# FLS_ADC_A_POWER_SUPPLY.net
KiCad netlist of a schematic drawn in Altium Designer
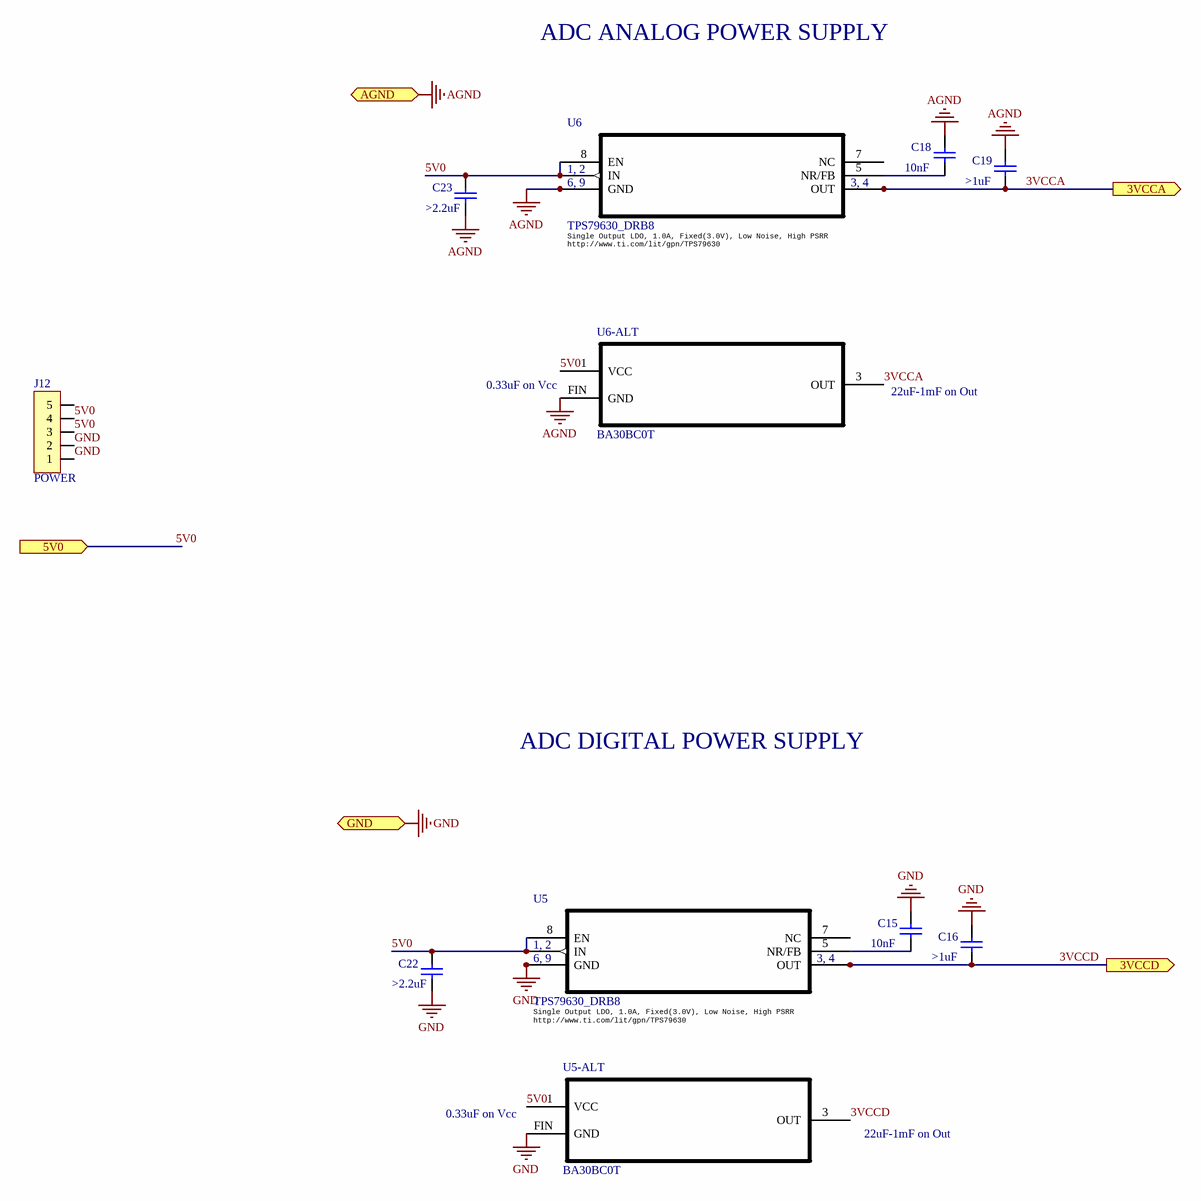
[diagram p0: FLS ADC_A POWER SUPPLY.SchDoc]

(export (version "E")
  (design (tool "Eeschema 10.0.6"))
  (components
    (comp (ref "C15")
      (value "10nF")
      (footprint "1608[0603]")
      (description "CAP CER 0.22UF 50V 10% X7R 0805")
      (fields
        (field (name "DIGI-KEY PART NUMBER") "587-1287-6-ND")
        (field (name "PUBLISHER") "Altium Limited")
      )
      (libsource (lib "Miscellaneous Devices") (part "Cap"))
    )
    (comp (ref "C16")
      (value ">1uF")
      (footprint "0805 slim outer")
      (description "CAP CER 0.22UF 50V 10% X7R 0805")
      (fields
        (field (name "DIGI-KEY PART NUMBER") "587-1287-6-ND")
        (field (name "PUBLISHER") "Altium Limited")
      )
      (libsource (lib "Miscellaneous Devices") (part "Cap"))
    )
    (comp (ref "C18")
      (value "10nF")
      (footprint "1608[0603]")
      (description "CAP CER 0.22UF 50V 10% X7R 0805")
      (fields
        (field (name "DIGI-KEY PART NUMBER") "587-1287-6-ND")
        (field (name "PUBLISHER") "Altium Limited")
      )
      (libsource (lib "Miscellaneous Devices") (part "Cap"))
    )
    (comp (ref "C19")
      (value ">1uF")
      (footprint "0805 slim outer")
      (description "CAP CER 0.22UF 50V 10% X7R 0805")
      (fields
        (field (name "DIGI-KEY PART NUMBER") "587-1287-6-ND")
        (field (name "PUBLISHER") "Altium Limited")
      )
      (libsource (lib "Miscellaneous Devices") (part "Cap"))
    )
    (comp (ref "C22")
      (value ">2.2uF")
      (footprint "1608[0603]")
      (description "CAP CER 0.22UF 50V 10% X7R 0805")
      (fields
        (field (name "DIGI-KEY PART NUMBER") "587-1287-6-ND")
        (field (name "PUBLISHER") "Altium Limited")
      )
      (libsource (lib "Miscellaneous Devices") (part "Cap"))
    )
    (comp (ref "C23")
      (value ">2.2uF")
      (footprint "1608[0603]")
      (description "CAP CER 0.22UF 50V 10% X7R 0805")
      (fields
        (field (name "DIGI-KEY PART NUMBER") "587-1287-6-ND")
        (field (name "PUBLISHER") "Altium Limited")
      )
      (libsource (lib "Miscellaneous Devices") (part "Cap"))
    )
    (comp (ref "J12") (value "POWER") (footprint "SIP5") (libsource (lib "FLS ADC_A") (part "CON5")))
    (comp (ref "U5")
      (value "TPS79630_DRB8")
      (footprint "DRB8_2P4X1P65")
      (description "Single Output LDO, 1.0A, Fixed(3.0V), Low Noise, High PSRR")
      (fields (field (name "DATASHEET URL") "http://www.ti.com/lit/gpn/TPS79630"))
      (libsource (lib "FLS ADC_A") (part "TPS79630_DRB8"))
    )
    (comp (ref "U5-ALT")
      (value "BA30BC0T")
      (footprint "TO252-3")
      (libsource (lib "FLS ADC_A") (part "BA30BC0T"))
    )
    (comp (ref "U6")
      (value "TPS79630_DRB8")
      (footprint "DRB8_2P4X1P65")
      (description "Single Output LDO, 1.0A, Fixed(3.0V), Low Noise, High PSRR")
      (fields (field (name "DATASHEET URL") "http://www.ti.com/lit/gpn/TPS79630"))
      (libsource (lib "FLS ADC_A") (part "TPS79630_DRB8"))
    )
    (comp (ref "U6-ALT")
      (value "BA30BC0T")
      (footprint "TO252-3")
      (libsource (lib "FLS ADC_A") (part "BA30BC0T"))
    )
  )
  (nets
    (net (code "1") (name "/3VCCA") (class "Default")
      (node (ref "C19") (pin "1") (pinfunction "1_1") (pintype "passive"))
      (node (ref "U6") (pin "3") (pinfunction "OUT_3") (pintype "passive"))
      (node (ref "U6") (pin "4") (pinfunction "OUT_4") (pintype "passive"))
      (node (ref "U6-ALT") (pin "3") (pinfunction "OUT_3") (pintype "passive"))
    )
    (net (code "2") (name "/3VCCD") (class "Default")
      (node (ref "C16") (pin "1") (pinfunction "1_1") (pintype "passive"))
      (node (ref "U5") (pin "3") (pinfunction "OUT_3") (pintype "passive"))
      (node (ref "U5") (pin "4") (pinfunction "OUT_4") (pintype "passive"))
      (node (ref "U5-ALT") (pin "3") (pinfunction "OUT_3") (pintype "passive"))
    )
    (net (code "3") (name "/5V0") (class "Default")
      (node (ref "C22") (pin "2") (pinfunction "2_2") (pintype "passive"))
      (node (ref "C23") (pin "2") (pinfunction "2_2") (pintype "passive"))
      (node (ref "J12") (pin "3") (pinfunction "3_3") (pintype "passive"))
      (node (ref "J12") (pin "4") (pinfunction "4_4") (pintype "passive"))
      (node (ref "U5") (pin "1") (pinfunction "IN_1") (pintype "output"))
      (node (ref "U5") (pin "2") (pinfunction "IN_2") (pintype "output"))
      (node (ref "U5") (pin "8") (pinfunction "EN_8") (pintype "passive"))
      (node (ref "U5-ALT") (pin "1") (pinfunction "VCC_1") (pintype "passive"))
      (node (ref "U6") (pin "1") (pinfunction "IN_1") (pintype "output"))
      (node (ref "U6") (pin "2") (pinfunction "IN_2") (pintype "output"))
      (node (ref "U6") (pin "8") (pinfunction "EN_8") (pintype "passive"))
      (node (ref "U6-ALT") (pin "1") (pinfunction "VCC_1") (pintype "passive"))
    )
    (net (code "4") (name "AGND") (class "Default")
      (node (ref "C18") (pin "2") (pinfunction "2_2") (pintype "passive"))
      (node (ref "C19") (pin "2") (pinfunction "2_2") (pintype "passive"))
      (node (ref "C23") (pin "1") (pinfunction "1_1") (pintype "passive"))
      (node (ref "U6") (pin "6") (pinfunction "GND_6") (pintype "power_in"))
      (node (ref "U6") (pin "9") (pinfunction "9_9") (pintype "power_in"))
      (node (ref "U6") (pin "V_1") (pinfunction "V_1_V_1") (pintype "power_in"))
      (node (ref "U6") (pin "V_2") (pinfunction "V_2_V_2") (pintype "power_in"))
      (node (ref "U6") (pin "V_3") (pinfunction "V_3_V_3") (pintype "power_in"))
      (node (ref "U6") (pin "V_4") (pinfunction "V_4_V_4") (pintype "power_in"))
      (node (ref "U6") (pin "V_5") (pinfunction "V_5_V_5") (pintype "power_in"))
      (node (ref "U6") (pin "V_6") (pinfunction "V_6_V_6") (pintype "power_in"))
      (node (ref "U6-ALT") (pin "FIN") (pinfunction "GND_FIN") (pintype "power_in"))
    )
    (net (code "5") (name "GND") (class "Default")
      (node (ref "C15") (pin "2") (pinfunction "2_2") (pintype "passive"))
      (node (ref "C16") (pin "2") (pinfunction "2_2") (pintype "passive"))
      (node (ref "C22") (pin "1") (pinfunction "1_1") (pintype "passive"))
      (node (ref "J12") (pin "1") (pinfunction "1_1") (pintype "passive"))
      (node (ref "J12") (pin "2") (pinfunction "2_2") (pintype "passive"))
      (node (ref "U5") (pin "6") (pinfunction "GND_6") (pintype "power_in"))
      (node (ref "U5") (pin "9") (pinfunction "9_9") (pintype "power_in"))
      (node (ref "U5") (pin "V_1") (pinfunction "V_1_V_1") (pintype "power_in"))
      (node (ref "U5") (pin "V_2") (pinfunction "V_2_V_2") (pintype "power_in"))
      (node (ref "U5") (pin "V_3") (pinfunction "V_3_V_3") (pintype "power_in"))
      (node (ref "U5") (pin "V_4") (pinfunction "V_4_V_4") (pintype "power_in"))
      (node (ref "U5") (pin "V_5") (pinfunction "V_5_V_5") (pintype "power_in"))
      (node (ref "U5") (pin "V_6") (pinfunction "V_6_V_6") (pintype "power_in"))
      (node (ref "U5-ALT") (pin "FIN") (pinfunction "GND_FIN") (pintype "power_in"))
    )
    (net (code "6") (name "Net-(U5-NR{slash}FB)") (class "Default")
      (node (ref "C15") (pin "1") (pinfunction "1_1") (pintype "passive"))
      (node (ref "U5") (pin "5") (pinfunction "NR/FB_5") (pintype "passive"))
    )
    (net (code "7") (name "Net-(U6-NR{slash}FB)") (class "Default")
      (node (ref "C18") (pin "1") (pinfunction "1_1") (pintype "passive"))
      (node (ref "U6") (pin "5") (pinfunction "NR/FB_5") (pintype "passive"))
    )
    (net (code "8") (name "unconnected-(J12-Pad5)") (class "Default")
      (node (ref "J12") (pin "5") (pinfunction "5_5") (pintype "passive"))
    )
    (net (code "9") (name "unconnected-(U5-NC-Pad7)") (class "Default")
      (node (ref "U5") (pin "7") (pinfunction "NC_7") (pintype "power_in"))
    )
    (net (code "10") (name "unconnected-(U6-NC-Pad7)") (class "Default")
      (node (ref "U6") (pin "7") (pinfunction "NC_7") (pintype "power_in"))
    )
  )
)
